# 4x_1206.net
KiCad netlist of a schematic drawn in EAGLE
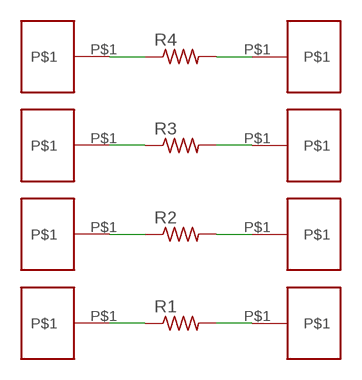
[diagram p0: schematic, sheet 1]

(export (version "E")
  (design (tool "Eeschema 10.0.6"))
  (components
    (comp (ref "R1")
      (value "R-US_R1206")
      (footprint "eagle-import:R1206")
      (libsource (lib "eagle-import") (part "R-US_R1206"))
    )
    (comp (ref "R2")
      (value "R-US_R1206")
      (footprint "eagle-import:R1206")
      (libsource (lib "eagle-import") (part "R-US_R1206"))
    )
    (comp (ref "R3")
      (value "R-US_R1206")
      (footprint "eagle-import:R1206")
      (libsource (lib "eagle-import") (part "R-US_R1206"))
    )
    (comp (ref "R4")
      (value "R-US_R1206")
      (footprint "eagle-import:R1206")
      (libsource (lib "eagle-import") (part "R-US_R1206"))
    )
    (comp (ref "U$1")
      (value "PAD100MIL")
      (footprint "eagle-import:100MIL_PAD")
      (libsource (lib "eagle-import") (part "PAD100MIL"))
    )
    (comp (ref "U$2")
      (value "PAD100MIL")
      (footprint "eagle-import:100MIL_PAD")
      (libsource (lib "eagle-import") (part "PAD100MIL"))
    )
    (comp (ref "U$3")
      (value "PAD100MIL")
      (footprint "eagle-import:100MIL_PAD")
      (libsource (lib "eagle-import") (part "PAD100MIL"))
    )
    (comp (ref "U$4")
      (value "PAD100MIL")
      (footprint "eagle-import:100MIL_PAD")
      (libsource (lib "eagle-import") (part "PAD100MIL"))
    )
    (comp (ref "U$5")
      (value "PAD100MIL")
      (footprint "eagle-import:100MIL_PAD")
      (libsource (lib "eagle-import") (part "PAD100MIL"))
    )
    (comp (ref "U$6")
      (value "PAD100MIL")
      (footprint "eagle-import:100MIL_PAD")
      (libsource (lib "eagle-import") (part "PAD100MIL"))
    )
    (comp (ref "U$7")
      (value "PAD100MIL")
      (footprint "eagle-import:100MIL_PAD")
      (libsource (lib "eagle-import") (part "PAD100MIL"))
    )
    (comp (ref "U$8")
      (value "PAD100MIL")
      (footprint "eagle-import:100MIL_PAD")
      (libsource (lib "eagle-import") (part "PAD100MIL"))
    )
  )
  (nets
    (net (code "1") (name "Net-(R1-Pad1)") (class "Default")
      (node (ref "R1") (pin "1") (pinfunction "1_1") (pintype "passive"))
      (node (ref "U$4") (pin "P$1") (pinfunction "P$1_P$1") (pintype "bidirectional"))
    )
    (net (code "2") (name "Net-(R1-Pad2)") (class "Default")
      (node (ref "R1") (pin "2") (pinfunction "2_2") (pintype "passive"))
      (node (ref "U$8") (pin "P$1") (pinfunction "P$1_P$1") (pintype "bidirectional"))
    )
    (net (code "3") (name "Net-(R2-Pad1)") (class "Default")
      (node (ref "R2") (pin "1") (pinfunction "1_1") (pintype "passive"))
      (node (ref "U$3") (pin "P$1") (pinfunction "P$1_P$1") (pintype "bidirectional"))
    )
    (net (code "4") (name "Net-(R2-Pad2)") (class "Default")
      (node (ref "R2") (pin "2") (pinfunction "2_2") (pintype "passive"))
      (node (ref "U$7") (pin "P$1") (pinfunction "P$1_P$1") (pintype "bidirectional"))
    )
    (net (code "5") (name "Net-(R3-Pad1)") (class "Default")
      (node (ref "R3") (pin "1") (pinfunction "1_1") (pintype "passive"))
      (node (ref "U$2") (pin "P$1") (pinfunction "P$1_P$1") (pintype "bidirectional"))
    )
    (net (code "6") (name "Net-(R3-Pad2)") (class "Default")
      (node (ref "R3") (pin "2") (pinfunction "2_2") (pintype "passive"))
      (node (ref "U$6") (pin "P$1") (pinfunction "P$1_P$1") (pintype "bidirectional"))
    )
    (net (code "7") (name "Net-(R4-Pad1)") (class "Default")
      (node (ref "R4") (pin "1") (pinfunction "1_1") (pintype "passive"))
      (node (ref "U$1") (pin "P$1") (pinfunction "P$1_P$1") (pintype "bidirectional"))
    )
    (net (code "8") (name "Net-(R4-Pad2)") (class "Default")
      (node (ref "R4") (pin "2") (pinfunction "2_2") (pintype "passive"))
      (node (ref "U$5") (pin "P$1") (pinfunction "P$1_P$1") (pintype "bidirectional"))
    )
  )
)
